# SCH-c-pad_2026-07-27.net
KiCad netlist of a schematic drawn in EasyEDA
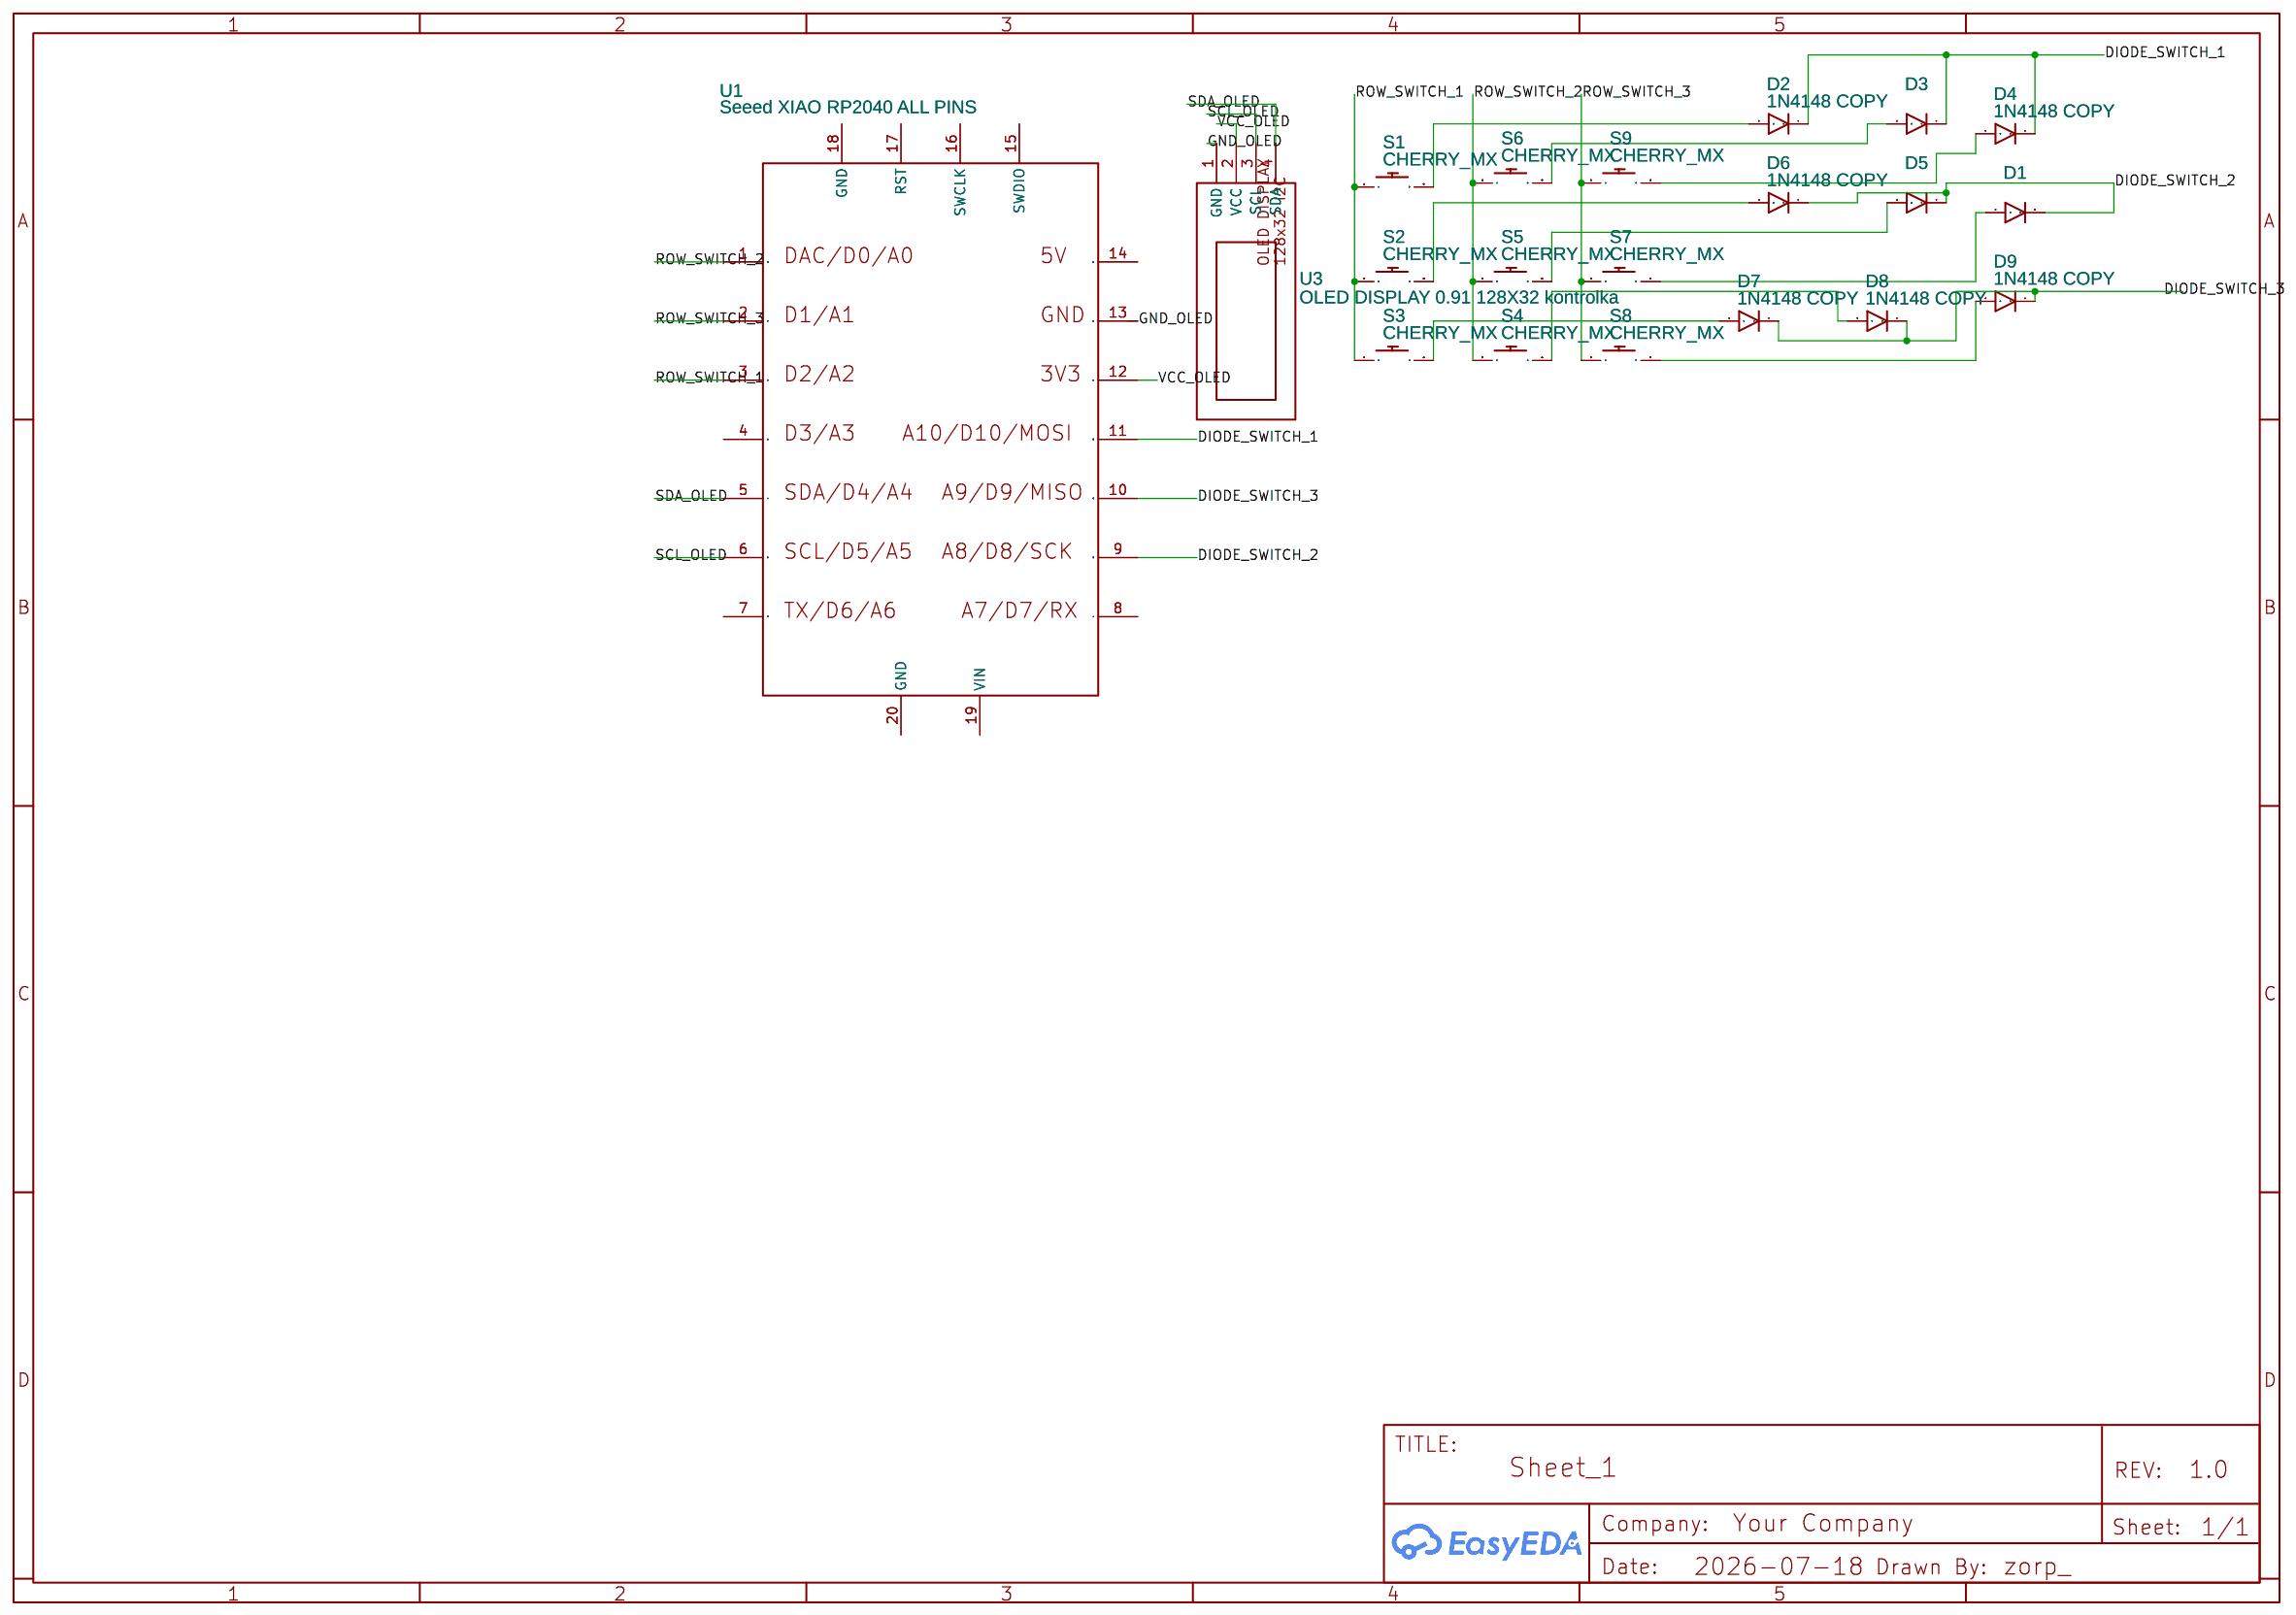
[diagram p0: schematic sheet]

(export (version "E")
  (design (tool "Eeschema 10.0.6"))
  (components
    (comp (ref "D1") (value "1N4148 COPY") (libsource (lib "") (part "1N4148 COPY")))
    (comp (ref "D2") (value "1N4148 COPY") (libsource (lib "") (part "1N4148 COPY")))
    (comp (ref "D3") (value "1N4148 COPY") (libsource (lib "") (part "1N4148 COPY")))
    (comp (ref "D4") (value "1N4148 COPY") (libsource (lib "") (part "1N4148 COPY")))
    (comp (ref "D5") (value "1N4148 COPY") (libsource (lib "") (part "1N4148 COPY")))
    (comp (ref "D6") (value "1N4148 COPY") (libsource (lib "") (part "1N4148 COPY")))
    (comp (ref "D7") (value "1N4148 COPY") (libsource (lib "") (part "1N4148 COPY")))
    (comp (ref "D8") (value "1N4148 COPY") (libsource (lib "") (part "1N4148 COPY")))
    (comp (ref "D9") (value "1N4148 COPY") (libsource (lib "") (part "1N4148 COPY")))
    (comp (ref "S1") (value "CHERRY_MX") (libsource (lib "") (part "CHERRY_MX")))
    (comp (ref "S2") (value "CHERRY_MX") (libsource (lib "") (part "CHERRY_MX")))
    (comp (ref "S3") (value "CHERRY_MX") (libsource (lib "") (part "CHERRY_MX")))
    (comp (ref "S4") (value "CHERRY_MX") (libsource (lib "") (part "CHERRY_MX")))
    (comp (ref "S5") (value "CHERRY_MX") (libsource (lib "") (part "CHERRY_MX")))
    (comp (ref "S6") (value "CHERRY_MX") (libsource (lib "") (part "CHERRY_MX")))
    (comp (ref "S7") (value "CHERRY_MX") (libsource (lib "") (part "CHERRY_MX")))
    (comp (ref "S8") (value "CHERRY_MX") (libsource (lib "") (part "CHERRY_MX")))
    (comp (ref "S9") (value "CHERRY_MX") (libsource (lib "") (part "CHERRY_MX")))
    (comp (ref "U1")
      (value "Seeed XIAO RP2040 ALL PINS")
      (fields (field (name "Manufacturer Part") "102010328") (field (name "Manufacturer") "Seeedstudio"))
      (libsource (lib "") (part "Seeed XIAO RP2040 ALL PINS"))
    )
    (comp (ref "U3")
      (value "OLED DISPLAY 0.91 128X32 kontrolka")
      (libsource (lib "") (part "OLED DISPLAY 0.91 128X32 kontrolka"))
    )
  )
  (nets
    (net (code "1") (name "/DIODE_SWITCH_1") (class "Default")
      (node (ref "D2") (pin "1") (pinfunction "1_1") (pintype "unspecified"))
      (node (ref "D3") (pin "1") (pinfunction "1_1") (pintype "unspecified"))
      (node (ref "D4") (pin "1") (pinfunction "1_1") (pintype "unspecified"))
      (node (ref "U1") (pin "11") (pinfunction "10_11") (pintype "unspecified"))
    )
    (net (code "2") (name "/DIODE_SWITCH_2") (class "Default")
      (node (ref "D1") (pin "1") (pinfunction "1_1") (pintype "unspecified"))
      (node (ref "D5") (pin "1") (pinfunction "1_1") (pintype "unspecified"))
      (node (ref "D6") (pin "1") (pinfunction "1_1") (pintype "unspecified"))
      (node (ref "U1") (pin "9") (pinfunction "8_9") (pintype "unspecified"))
    )
    (net (code "3") (name "/DIODE_SWITCH_3") (class "Default")
      (node (ref "D7") (pin "1") (pinfunction "1_1") (pintype "unspecified"))
      (node (ref "D8") (pin "1") (pinfunction "1_1") (pintype "unspecified"))
      (node (ref "D9") (pin "1") (pinfunction "1_1") (pintype "unspecified"))
      (node (ref "U1") (pin "10") (pinfunction "9_10") (pintype "unspecified"))
    )
    (net (code "4") (name "/GND_OLED") (class "Default")
      (node (ref "U1") (pin "13") (pinfunction "12_13") (pintype "unspecified"))
      (node (ref "U3") (pin "1") (pinfunction "GND_1") (pintype "passive"))
    )
    (net (code "5") (name "/ROW_SWITCH_1") (class "Default")
      (node (ref "S1") (pin "S1") (pinfunction "1_S1") (pintype "bidirectional"))
      (node (ref "S2") (pin "S1") (pinfunction "1_S1") (pintype "bidirectional"))
      (node (ref "S3") (pin "S1") (pinfunction "1_S1") (pintype "bidirectional"))
      (node (ref "U1") (pin "3") (pinfunction "2_3") (pintype "unspecified"))
    )
    (net (code "6") (name "/ROW_SWITCH_2") (class "Default")
      (node (ref "S4") (pin "S1") (pinfunction "1_S1") (pintype "bidirectional"))
      (node (ref "S5") (pin "S1") (pinfunction "1_S1") (pintype "bidirectional"))
      (node (ref "S6") (pin "S1") (pinfunction "1_S1") (pintype "bidirectional"))
      (node (ref "U1") (pin "1") (pinfunction "0_1") (pintype "unspecified"))
    )
    (net (code "7") (name "/ROW_SWITCH_3") (class "Default")
      (node (ref "S7") (pin "S1") (pinfunction "1_S1") (pintype "bidirectional"))
      (node (ref "S8") (pin "S1") (pinfunction "1_S1") (pintype "bidirectional"))
      (node (ref "S9") (pin "S1") (pinfunction "1_S1") (pintype "bidirectional"))
      (node (ref "U1") (pin "2") (pinfunction "1_2") (pintype "unspecified"))
    )
    (net (code "8") (name "/SCL_OLED") (class "Default")
      (node (ref "U1") (pin "6") (pinfunction "5_6") (pintype "unspecified"))
      (node (ref "U3") (pin "3") (pinfunction "SCL_3") (pintype "input"))
    )
    (net (code "9") (name "/SDA_OLED") (class "Default")
      (node (ref "U1") (pin "5") (pinfunction "4_5") (pintype "unspecified"))
      (node (ref "U3") (pin "4") (pinfunction "SDA_4") (pintype "input"))
    )
    (net (code "10") (name "/VCC_OLED") (class "Default")
      (node (ref "U1") (pin "12") (pinfunction "11_12") (pintype "unspecified"))
      (node (ref "U3") (pin "2") (pinfunction "VCC_2") (pintype "passive"))
    )
    (net (code "11") (name "Net-(S1-2)") (class "Default")
      (node (ref "D2") (pin "2") (pinfunction "2_2") (pintype "unspecified"))
      (node (ref "S1") (pin "S2") (pinfunction "2_S2") (pintype "bidirectional"))
    )
    (net (code "12") (name "Net-(S2-2)") (class "Default")
      (node (ref "D6") (pin "2") (pinfunction "2_2") (pintype "unspecified"))
      (node (ref "S2") (pin "S2") (pinfunction "2_S2") (pintype "bidirectional"))
    )
    (net (code "13") (name "Net-(S3-2)") (class "Default")
      (node (ref "D7") (pin "2") (pinfunction "2_2") (pintype "unspecified"))
      (node (ref "S3") (pin "S2") (pinfunction "2_S2") (pintype "bidirectional"))
    )
    (net (code "14") (name "Net-(S4-2)") (class "Default")
      (node (ref "D8") (pin "2") (pinfunction "2_2") (pintype "unspecified"))
      (node (ref "S4") (pin "S2") (pinfunction "2_S2") (pintype "bidirectional"))
    )
    (net (code "15") (name "Net-(S5-2)") (class "Default")
      (node (ref "D5") (pin "2") (pinfunction "2_2") (pintype "unspecified"))
      (node (ref "S5") (pin "S2") (pinfunction "2_S2") (pintype "bidirectional"))
    )
    (net (code "16") (name "Net-(S6-2)") (class "Default")
      (node (ref "D3") (pin "2") (pinfunction "2_2") (pintype "unspecified"))
      (node (ref "S6") (pin "S2") (pinfunction "2_S2") (pintype "bidirectional"))
    )
    (net (code "17") (name "Net-(S7-2)") (class "Default")
      (node (ref "D1") (pin "2") (pinfunction "2_2") (pintype "unspecified"))
      (node (ref "S7") (pin "S2") (pinfunction "2_S2") (pintype "bidirectional"))
    )
    (net (code "18") (name "Net-(S8-2)") (class "Default")
      (node (ref "D9") (pin "2") (pinfunction "2_2") (pintype "unspecified"))
      (node (ref "S8") (pin "S2") (pinfunction "2_S2") (pintype "bidirectional"))
    )
    (net (code "19") (name "Net-(S9-2)") (class "Default")
      (node (ref "D4") (pin "2") (pinfunction "2_2") (pintype "unspecified"))
      (node (ref "S9") (pin "S2") (pinfunction "2_S2") (pintype "bidirectional"))
    )
    (net (code "20") (name "unconnected-(U1-3-Pad4)") (class "Default")
      (node (ref "U1") (pin "4") (pinfunction "3_4") (pintype "unspecified"))
    )
    (net (code "21") (name "unconnected-(U1-6-Pad7)") (class "Default")
      (node (ref "U1") (pin "7") (pinfunction "6_7") (pintype "unspecified"))
    )
    (net (code "22") (name "unconnected-(U1-7-Pad8)") (class "Default")
      (node (ref "U1") (pin "8") (pinfunction "7_8") (pintype "unspecified"))
    )
    (net (code "23") (name "unconnected-(U1-13-Pad14)") (class "Default")
      (node (ref "U1") (pin "14") (pinfunction "13_14") (pintype "unspecified"))
    )
    (net (code "24") (name "unconnected-(U1-GND-Pad18)") (class "Default")
      (node (ref "U1") (pin "18") (pinfunction "GND_18") (pintype "unspecified"))
    )
    (net (code "25") (name "unconnected-(U1-GND-Pad20)") (class "Default")
      (node (ref "U1") (pin "20") (pinfunction "GND_20") (pintype "unspecified"))
    )
    (net (code "26") (name "unconnected-(U1-RST-Pad17)") (class "Default")
      (node (ref "U1") (pin "17") (pinfunction "RST_17") (pintype "unspecified"))
    )
    (net (code "27") (name "unconnected-(U1-SWCLK-Pad16)") (class "Default")
      (node (ref "U1") (pin "16") (pinfunction "SWCLK_16") (pintype "unspecified"))
    )
    (net (code "28") (name "unconnected-(U1-SWDIO-Pad15)") (class "Default")
      (node (ref "U1") (pin "15") (pinfunction "SWDIO_15") (pintype "unspecified"))
    )
    (net (code "29") (name "unconnected-(U1-VIN-Pad19)") (class "Default")
      (node (ref "U1") (pin "19") (pinfunction "VIN_19") (pintype "unspecified"))
    )
  )
)
